# Servo_tester_rev1.net
KiCad netlist of a schematic drawn in EAGLE
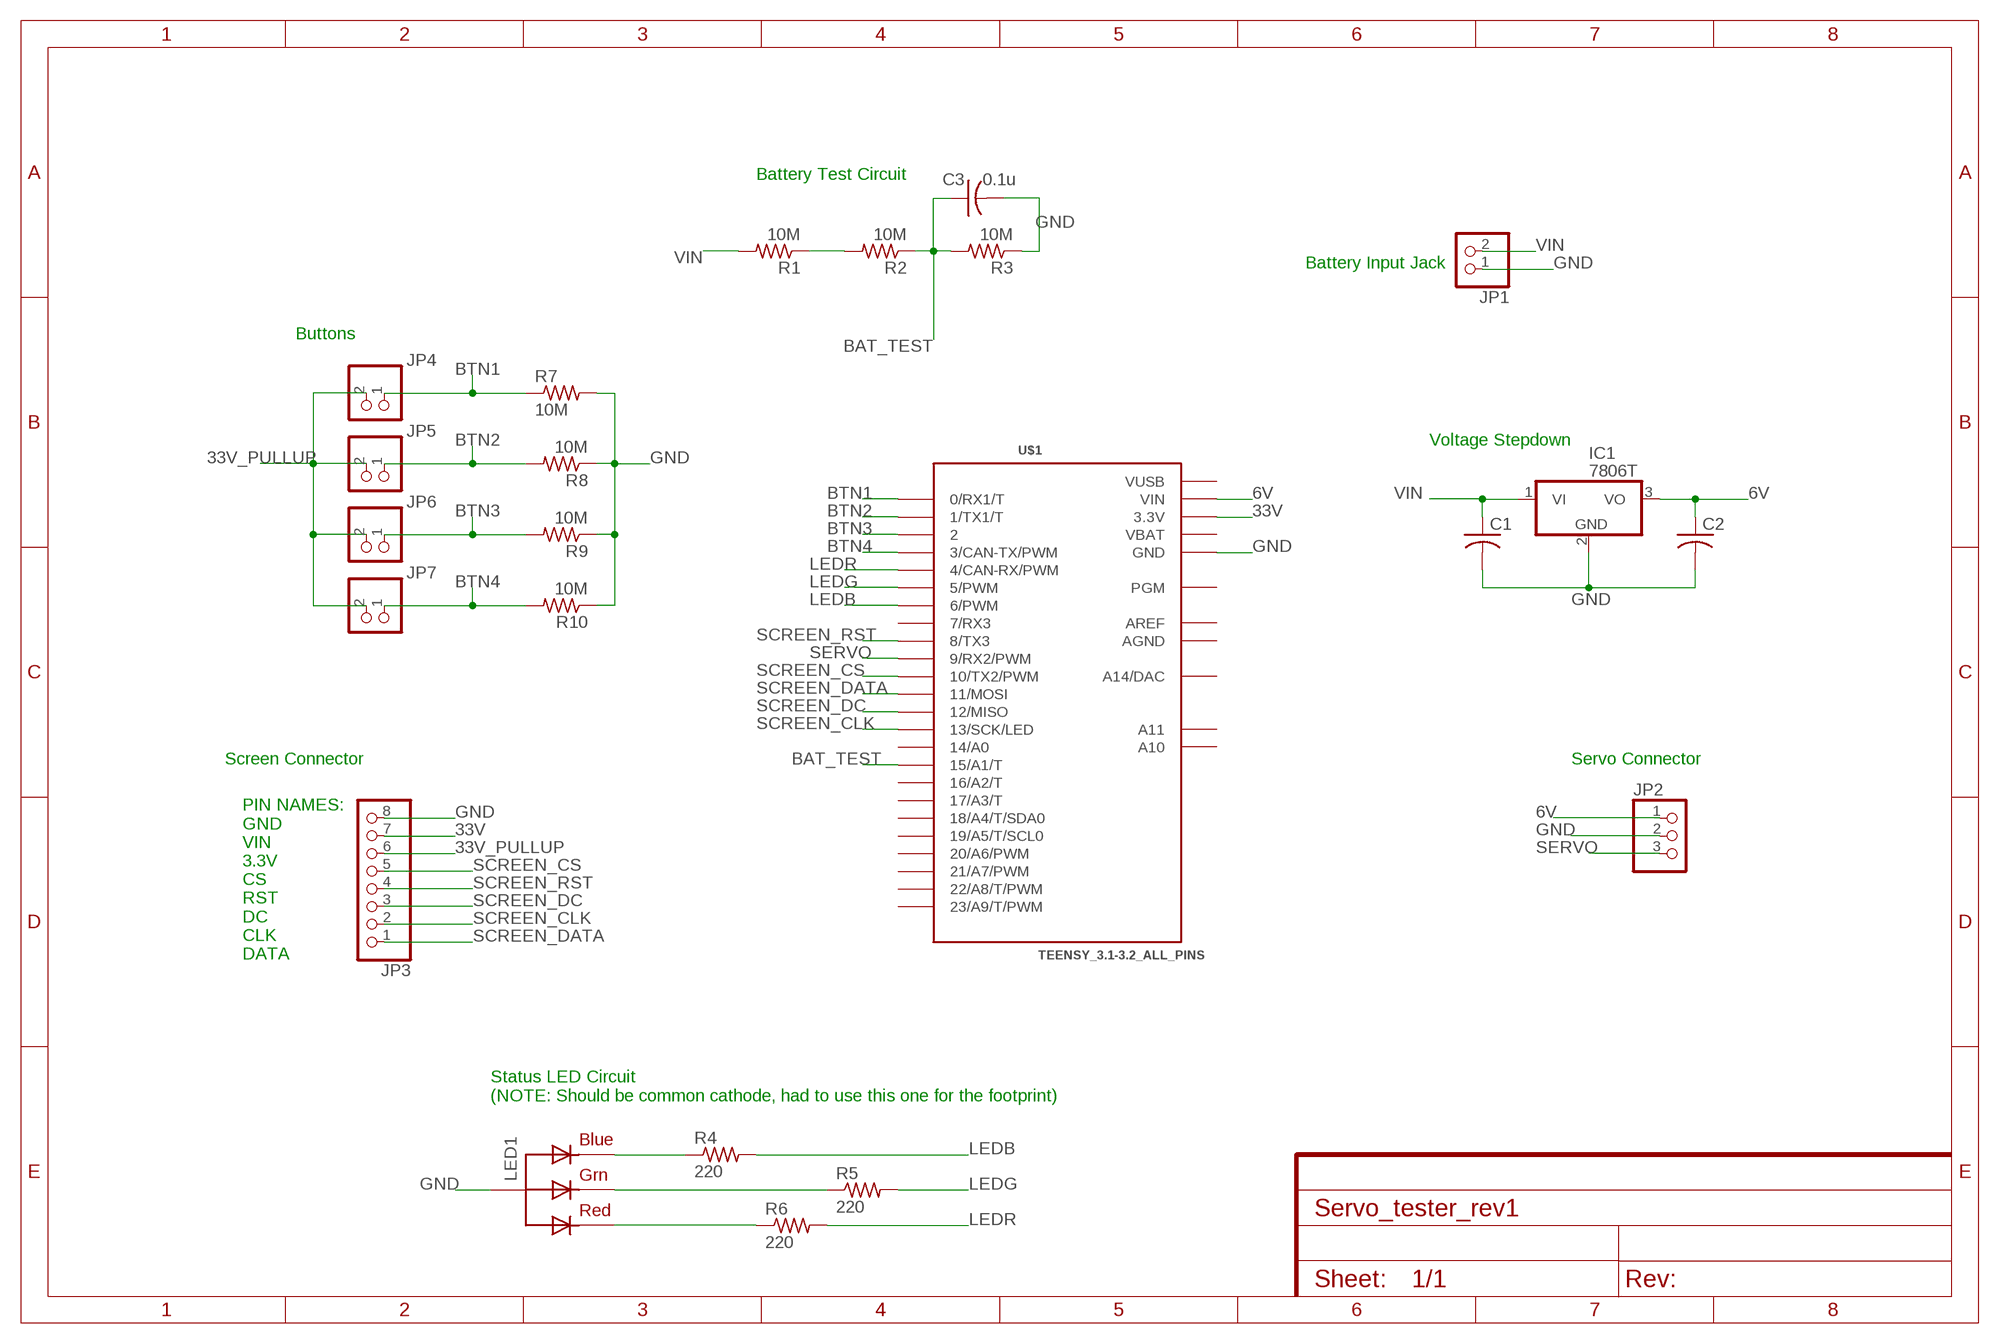
[diagram p0: schematic, sheet 1]

(export (version "E")
  (design (tool "Eeschema 10.0.6"))
  (components
    (comp (ref "C1")
      (value "C-US050-024X044")
      (footprint "eagle-import:C050-024X044")
      (libsource (lib "eagle-import") (part "C-US050-024X044"))
    )
    (comp (ref "C2")
      (value "C-US050-024X044")
      (footprint "eagle-import:C050-024X044")
      (libsource (lib "eagle-import") (part "C-US050-024X044"))
    )
    (comp (ref "C3")
      (value "0.1u")
      (footprint "eagle-import:C050-024X044")
      (libsource (lib "eagle-import") (part "C-US050-024X044"))
    )
    (comp (ref "IC1")
      (value "7806T")
      (footprint "eagle-import:TO220H")
      (libsource (lib "eagle-import") (part "78T06"))
    )
    (comp (ref "JP1")
      (value "HEADER-1X2ROUND")
      (footprint "eagle-import:1X02_ROUND")
      (libsource (lib "eagle-import") (part "HEADER-1X2ROUND"))
    )
    (comp (ref "JP2")
      (value "HEADER-1X3ROUND")
      (footprint "eagle-import:1X03_ROUND")
      (libsource (lib "eagle-import") (part "HEADER-1X3ROUND"))
    )
    (comp (ref "JP3")
      (value "HEADER-1X870MIL")
      (footprint "eagle-import:1X08_ROUND_70")
      (libsource (lib "eagle-import") (part "HEADER-1X870MIL"))
    )
    (comp (ref "JP4")
      (value "HEADER-1X2ROUND")
      (footprint "eagle-import:1X02_ROUND")
      (libsource (lib "eagle-import") (part "HEADER-1X2ROUND"))
    )
    (comp (ref "JP5")
      (value "HEADER-1X2ROUND")
      (footprint "eagle-import:1X02_ROUND")
      (libsource (lib "eagle-import") (part "HEADER-1X2ROUND"))
    )
    (comp (ref "JP6")
      (value "HEADER-1X2ROUND")
      (footprint "eagle-import:1X02_ROUND")
      (libsource (lib "eagle-import") (part "HEADER-1X2ROUND"))
    )
    (comp (ref "JP7")
      (value "HEADER-1X2ROUND")
      (footprint "eagle-import:1X02_ROUND")
      (libsource (lib "eagle-import") (part "HEADER-1X2ROUND"))
    )
    (comp (ref "LED1")
      (value "RGBLED_CA-5MM")
      (footprint "eagle-import:LED5MMRGB")
      (libsource (lib "eagle-import") (part "RGBLED_CA-5MM"))
    )
    (comp (ref "R1")
      (value "10M")
      (footprint "eagle-import:0204_5")
      (libsource (lib "eagle-import") (part "R-US_0204/5"))
    )
    (comp (ref "R2")
      (value "10M")
      (footprint "eagle-import:0204_5")
      (libsource (lib "eagle-import") (part "R-US_0204/5"))
    )
    (comp (ref "R3")
      (value "10M")
      (footprint "eagle-import:0204_5")
      (libsource (lib "eagle-import") (part "R-US_0204/5"))
    )
    (comp (ref "R4")
      (value "220")
      (footprint "eagle-import:0204_5")
      (libsource (lib "eagle-import") (part "R-US_0204/5"))
    )
    (comp (ref "R5")
      (value "220")
      (footprint "eagle-import:0204_5")
      (libsource (lib "eagle-import") (part "R-US_0204/5"))
    )
    (comp (ref "R6")
      (value "220")
      (footprint "eagle-import:0204_5")
      (libsource (lib "eagle-import") (part "R-US_0204/5"))
    )
    (comp (ref "R7")
      (value "10M")
      (footprint "eagle-import:0204_5")
      (libsource (lib "eagle-import") (part "R-US_0204/5"))
    )
    (comp (ref "R8")
      (value "10M")
      (footprint "eagle-import:0204_5")
      (libsource (lib "eagle-import") (part "R-US_0204/5"))
    )
    (comp (ref "R9")
      (value "10M")
      (footprint "eagle-import:0204_5")
      (libsource (lib "eagle-import") (part "R-US_0204/5"))
    )
    (comp (ref "R10")
      (value "10M")
      (footprint "eagle-import:0204_5")
      (libsource (lib "eagle-import") (part "R-US_0204/5"))
    )
    (comp (ref "U$1")
      (value "TEENSY_3.1-3.2_ALL_PINS")
      (footprint "eagle-import:TEENSY_3.0-3.2&LC_ALL_PINS")
      (libsource (lib "eagle-import") (part "TEENSY_3.1-3.2_ALL_PINS"))
    )
  )
  (nets
    (net (code "1") (name "/6V") (class "Default")
      (node (ref "C2") (pin "1") (pinfunction "1_1") (pintype "passive"))
      (node (ref "IC1") (pin "3") (pinfunction "VO_3") (pintype "passive"))
      (node (ref "JP2") (pin "1") (pinfunction "1_1") (pintype "passive"))
      (node (ref "U$1") (pin "VIN") (pinfunction "VIN_VIN") (pintype "power_in"))
    )
    (net (code "2") (name "/33V") (class "Default")
      (node (ref "JP3") (pin "7") (pinfunction "7_7") (pintype "passive"))
      (node (ref "U$1") (pin "3.3V") (pinfunction "3.3V_3.3V") (pintype "power_in"))
      (node (ref "U$1") (pin "3.3V1") (pinfunction "3.3V_3.3V1") (pintype "power_in"))
    )
    (net (code "3") (name "/33V_PULLUP") (class "Default")
      (node (ref "JP3") (pin "6") (pinfunction "6_6") (pintype "passive"))
      (node (ref "JP4") (pin "2") (pinfunction "2_2") (pintype "passive"))
      (node (ref "JP5") (pin "2") (pinfunction "2_2") (pintype "passive"))
      (node (ref "JP6") (pin "2") (pinfunction "2_2") (pintype "passive"))
      (node (ref "JP7") (pin "2") (pinfunction "2_2") (pintype "passive"))
    )
    (net (code "4") (name "/AGND") (class "Default")
      (node (ref "U$1") (pin "AGND") (pinfunction "AGND_AGND") (pintype "power_in"))
    )
    (net (code "5") (name "/AREF") (class "Default")
      (node (ref "U$1") (pin "AREF") (pinfunction "AREF_AREF") (pintype "power_in"))
    )
    (net (code "6") (name "/BAT_TEST") (class "Default")
      (node (ref "C3") (pin "1") (pinfunction "1_1") (pintype "passive"))
      (node (ref "R2") (pin "1") (pinfunction "1_1") (pintype "passive"))
      (node (ref "R3") (pin "2") (pinfunction "2_2") (pintype "passive"))
      (node (ref "U$1") (pin "15/A1") (pinfunction "15/A1/T_15/A1") (pintype "bidirectional"))
    )
    (net (code "7") (name "/BTN1") (class "Default")
      (node (ref "JP4") (pin "1") (pinfunction "1_1") (pintype "passive"))
      (node (ref "R7") (pin "1") (pinfunction "1_1") (pintype "passive"))
      (node (ref "U$1") (pin "0") (pinfunction "0/RX1/T_0") (pintype "bidirectional"))
    )
    (net (code "8") (name "/BTN2") (class "Default")
      (node (ref "JP5") (pin "1") (pinfunction "1_1") (pintype "passive"))
      (node (ref "R8") (pin "2") (pinfunction "2_2") (pintype "passive"))
      (node (ref "U$1") (pin "1") (pinfunction "1/TX1/T_1") (pintype "bidirectional"))
    )
    (net (code "9") (name "/BTN3") (class "Default")
      (node (ref "JP6") (pin "1") (pinfunction "1_1") (pintype "passive"))
      (node (ref "R9") (pin "2") (pinfunction "2_2") (pintype "passive"))
      (node (ref "U$1") (pin "2") (pinfunction "2_2") (pintype "bidirectional"))
    )
    (net (code "10") (name "/BTN4") (class "Default")
      (node (ref "JP7") (pin "1") (pinfunction "1_1") (pintype "passive"))
      (node (ref "R10") (pin "2") (pinfunction "2_2") (pintype "passive"))
      (node (ref "U$1") (pin "3") (pinfunction "3/CAN-TX/PWM_3") (pintype "bidirectional"))
    )
    (net (code "11") (name "/GND") (class "Default")
      (node (ref "C1") (pin "2") (pinfunction "2_2") (pintype "passive"))
      (node (ref "C2") (pin "2") (pinfunction "2_2") (pintype "passive"))
      (node (ref "C3") (pin "2") (pinfunction "2_2") (pintype "passive"))
      (node (ref "IC1") (pin "2") (pinfunction "GND_2") (pintype "passive"))
      (node (ref "JP1") (pin "1") (pinfunction "1_1") (pintype "passive"))
      (node (ref "JP2") (pin "2") (pinfunction "2_2") (pintype "passive"))
      (node (ref "JP3") (pin "8") (pinfunction "8_8") (pintype "passive"))
      (node (ref "LED1") (pin "2") (pinfunction "VCC_2") (pintype "bidirectional"))
      (node (ref "R10") (pin "1") (pinfunction "1_1") (pintype "passive"))
      (node (ref "R3") (pin "1") (pinfunction "1_1") (pintype "passive"))
      (node (ref "R7") (pin "2") (pinfunction "2_2") (pintype "passive"))
      (node (ref "R8") (pin "1") (pinfunction "1_1") (pintype "passive"))
      (node (ref "R9") (pin "1") (pinfunction "1_1") (pintype "passive"))
      (node (ref "U$1") (pin "GND") (pinfunction "GND_GND") (pintype "power_in"))
      (node (ref "U$1") (pin "GND1") (pinfunction "GND_GND1") (pintype "power_in"))
    )
    (net (code "12") (name "/LEDB") (class "Default")
      (node (ref "R4") (pin "2") (pinfunction "2_2") (pintype "passive"))
      (node (ref "U$1") (pin "6") (pinfunction "6/PWM_6") (pintype "bidirectional"))
    )
    (net (code "13") (name "/LEDG") (class "Default")
      (node (ref "R5") (pin "2") (pinfunction "2_2") (pintype "passive"))
      (node (ref "U$1") (pin "5") (pinfunction "5/PWM_5") (pintype "bidirectional"))
    )
    (net (code "14") (name "/LEDR") (class "Default")
      (node (ref "R6") (pin "2") (pinfunction "2_2") (pintype "passive"))
      (node (ref "U$1") (pin "4") (pinfunction "4/CAN-RX/PWM_4") (pintype "bidirectional"))
    )
    (net (code "15") (name "/SCREEN_CLK") (class "Default")
      (node (ref "JP3") (pin "2") (pinfunction "2_2") (pintype "passive"))
      (node (ref "U$1") (pin "13") (pinfunction "13/SCK/LED_13") (pintype "bidirectional"))
    )
    (net (code "16") (name "/SCREEN_CS") (class "Default")
      (node (ref "JP3") (pin "5") (pinfunction "5_5") (pintype "passive"))
      (node (ref "U$1") (pin "10") (pinfunction "10/TX2/PWM_10") (pintype "bidirectional"))
    )
    (net (code "17") (name "/SCREEN_DATA") (class "Default")
      (node (ref "JP3") (pin "1") (pinfunction "1_1") (pintype "passive"))
      (node (ref "U$1") (pin "11") (pinfunction "11/MOSI_11") (pintype "bidirectional"))
    )
    (net (code "18") (name "/SCREEN_DC") (class "Default")
      (node (ref "JP3") (pin "3") (pinfunction "3_3") (pintype "passive"))
      (node (ref "U$1") (pin "12") (pinfunction "12/MISO_12") (pintype "bidirectional"))
    )
    (net (code "19") (name "/SCREEN_RST") (class "Default")
      (node (ref "JP3") (pin "4") (pinfunction "4_4") (pintype "passive"))
      (node (ref "U$1") (pin "8") (pinfunction "8/TX3_8") (pintype "bidirectional"))
    )
    (net (code "20") (name "/SERVO") (class "Default")
      (node (ref "JP2") (pin "3") (pinfunction "3_3") (pintype "passive"))
      (node (ref "U$1") (pin "9") (pinfunction "9/RX2/PWM_9") (pintype "bidirectional"))
    )
    (net (code "21") (name "/VBAT") (class "Default")
      (node (ref "U$1") (pin "VBAT") (pinfunction "VBAT_VBAT") (pintype "power_in"))
    )
    (net (code "22") (name "/VIN") (class "Default")
      (node (ref "C1") (pin "1") (pinfunction "1_1") (pintype "passive"))
      (node (ref "IC1") (pin "1") (pinfunction "VI_1") (pintype "input"))
      (node (ref "JP1") (pin "2") (pinfunction "2_2") (pintype "passive"))
      (node (ref "R1") (pin "2") (pinfunction "2_2") (pintype "passive"))
    )
    (net (code "23") (name "/VUSB") (class "Default")
      (node (ref "U$1") (pin "VUSB") (pinfunction "VUSB_VUSB") (pintype "power_in"))
    )
    (net (code "24") (name "Net-(LED1-BLUE)") (class "Default")
      (node (ref "LED1") (pin "4") (pinfunction "BLUE_4") (pintype "bidirectional"))
      (node (ref "R4") (pin "1") (pinfunction "1_1") (pintype "passive"))
    )
    (net (code "25") (name "Net-(LED1-GREEN)") (class "Default")
      (node (ref "LED1") (pin "3") (pinfunction "GREEN_3") (pintype "bidirectional"))
      (node (ref "R5") (pin "1") (pinfunction "1_1") (pintype "passive"))
    )
    (net (code "26") (name "Net-(LED1-RED)") (class "Default")
      (node (ref "LED1") (pin "1") (pinfunction "RED_1") (pintype "bidirectional"))
      (node (ref "R6") (pin "1") (pinfunction "1_1") (pintype "passive"))
    )
    (net (code "27") (name "Net-(R1-Pad1)") (class "Default")
      (node (ref "R1") (pin "1") (pinfunction "1_1") (pintype "passive"))
      (node (ref "R2") (pin "2") (pinfunction "2_2") (pintype "passive"))
    )
    (net (code "28") (name "unconnected-(U$1-7{slash}RX3-Pad7)") (class "Default")
      (node (ref "U$1") (pin "7") (pinfunction "7/RX3_7") (pintype "bidirectional"))
    )
    (net (code "29") (name "unconnected-(U$1-16{slash}A2{slash}T-Pad16{slash}A2)") (class "Default")
      (node (ref "U$1") (pin "16/A2") (pinfunction "16/A2/T_16/A2") (pintype "bidirectional"))
    )
    (net (code "30") (name "unconnected-(U$1-17{slash}A3{slash}T-Pad17{slash}A3)") (class "Default")
      (node (ref "U$1") (pin "17/A3") (pinfunction "17/A3/T_17/A3") (pintype "bidirectional"))
    )
    (net (code "31") (name "unconnected-(U$1-18{slash}A4{slash}T{slash}SDA0-Pad18{slash}A4)") (class "Default")
      (node (ref "U$1") (pin "18/A4") (pinfunction "18/A4/T/SDA0_18/A4") (pintype "bidirectional"))
    )
    (net (code "32") (name "unconnected-(U$1-19{slash}A5{slash}T{slash}SCL0-Pad19{slash}A5)") (class "Default")
      (node (ref "U$1") (pin "19/A5") (pinfunction "19/A5/T/SCL0_19/A5") (pintype "bidirectional"))
    )
    (net (code "33") (name "unconnected-(U$1-20{slash}A6{slash}PWM-Pad20{slash}A6)") (class "Default")
      (node (ref "U$1") (pin "20/A6") (pinfunction "20/A6/PWM_20/A6") (pintype "bidirectional"))
    )
    (net (code "34") (name "unconnected-(U$1-21{slash}A7{slash}PWM-Pad21{slash}A7)") (class "Default")
      (node (ref "U$1") (pin "21/A7") (pinfunction "21/A7/PWM_21/A7") (pintype "bidirectional"))
    )
    (net (code "35") (name "unconnected-(U$1-22{slash}A8{slash}T{slash}PWM-Pad22{slash}A8)") (class "Default")
      (node (ref "U$1") (pin "22/A8") (pinfunction "22/A8/T/PWM_22/A8") (pintype "bidirectional"))
    )
    (net (code "36") (name "unconnected-(U$1-23{slash}A9{slash}T{slash}PWM-Pad23{slash}A9)") (class "Default")
      (node (ref "U$1") (pin "23/A9") (pinfunction "23/A9/T/PWM_23/A9") (pintype "bidirectional"))
    )
    (net (code "37") (name "unconnected-(U$1-A14{slash}DAC-PadRESET{slash}DAC)") (class "Default")
      (node (ref "U$1") (pin "RESET/DAC") (pinfunction "A14/DAC_RESET/DAC") (pintype "bidirectional"))
    )
    (net (code "38") (name "unconnected-(U$1-Pad14{slash}A0)") (class "Default")
      (node (ref "U$1") (pin "14/A0") (pinfunction "14/A0_14/A0") (pintype "bidirectional"))
    )
    (net (code "39") (name "unconnected-(U$1-PadA10)") (class "Default")
      (node (ref "U$1") (pin "A10") (pinfunction "A10_A10") (pintype "bidirectional"))
    )
    (net (code "40") (name "unconnected-(U$1-PadA11)") (class "Default")
      (node (ref "U$1") (pin "A11") (pinfunction "A11_A11") (pintype "bidirectional"))
    )
    (net (code "41") (name "unconnected-(U$1-PadPGM)") (class "Default")
      (node (ref "U$1") (pin "PGM") (pinfunction "PGM_PGM") (pintype "bidirectional"))
    )
  )
)
